# Carrier_Motor_Driver.net
KiCad netlist of a schematic drawn in EAGLE
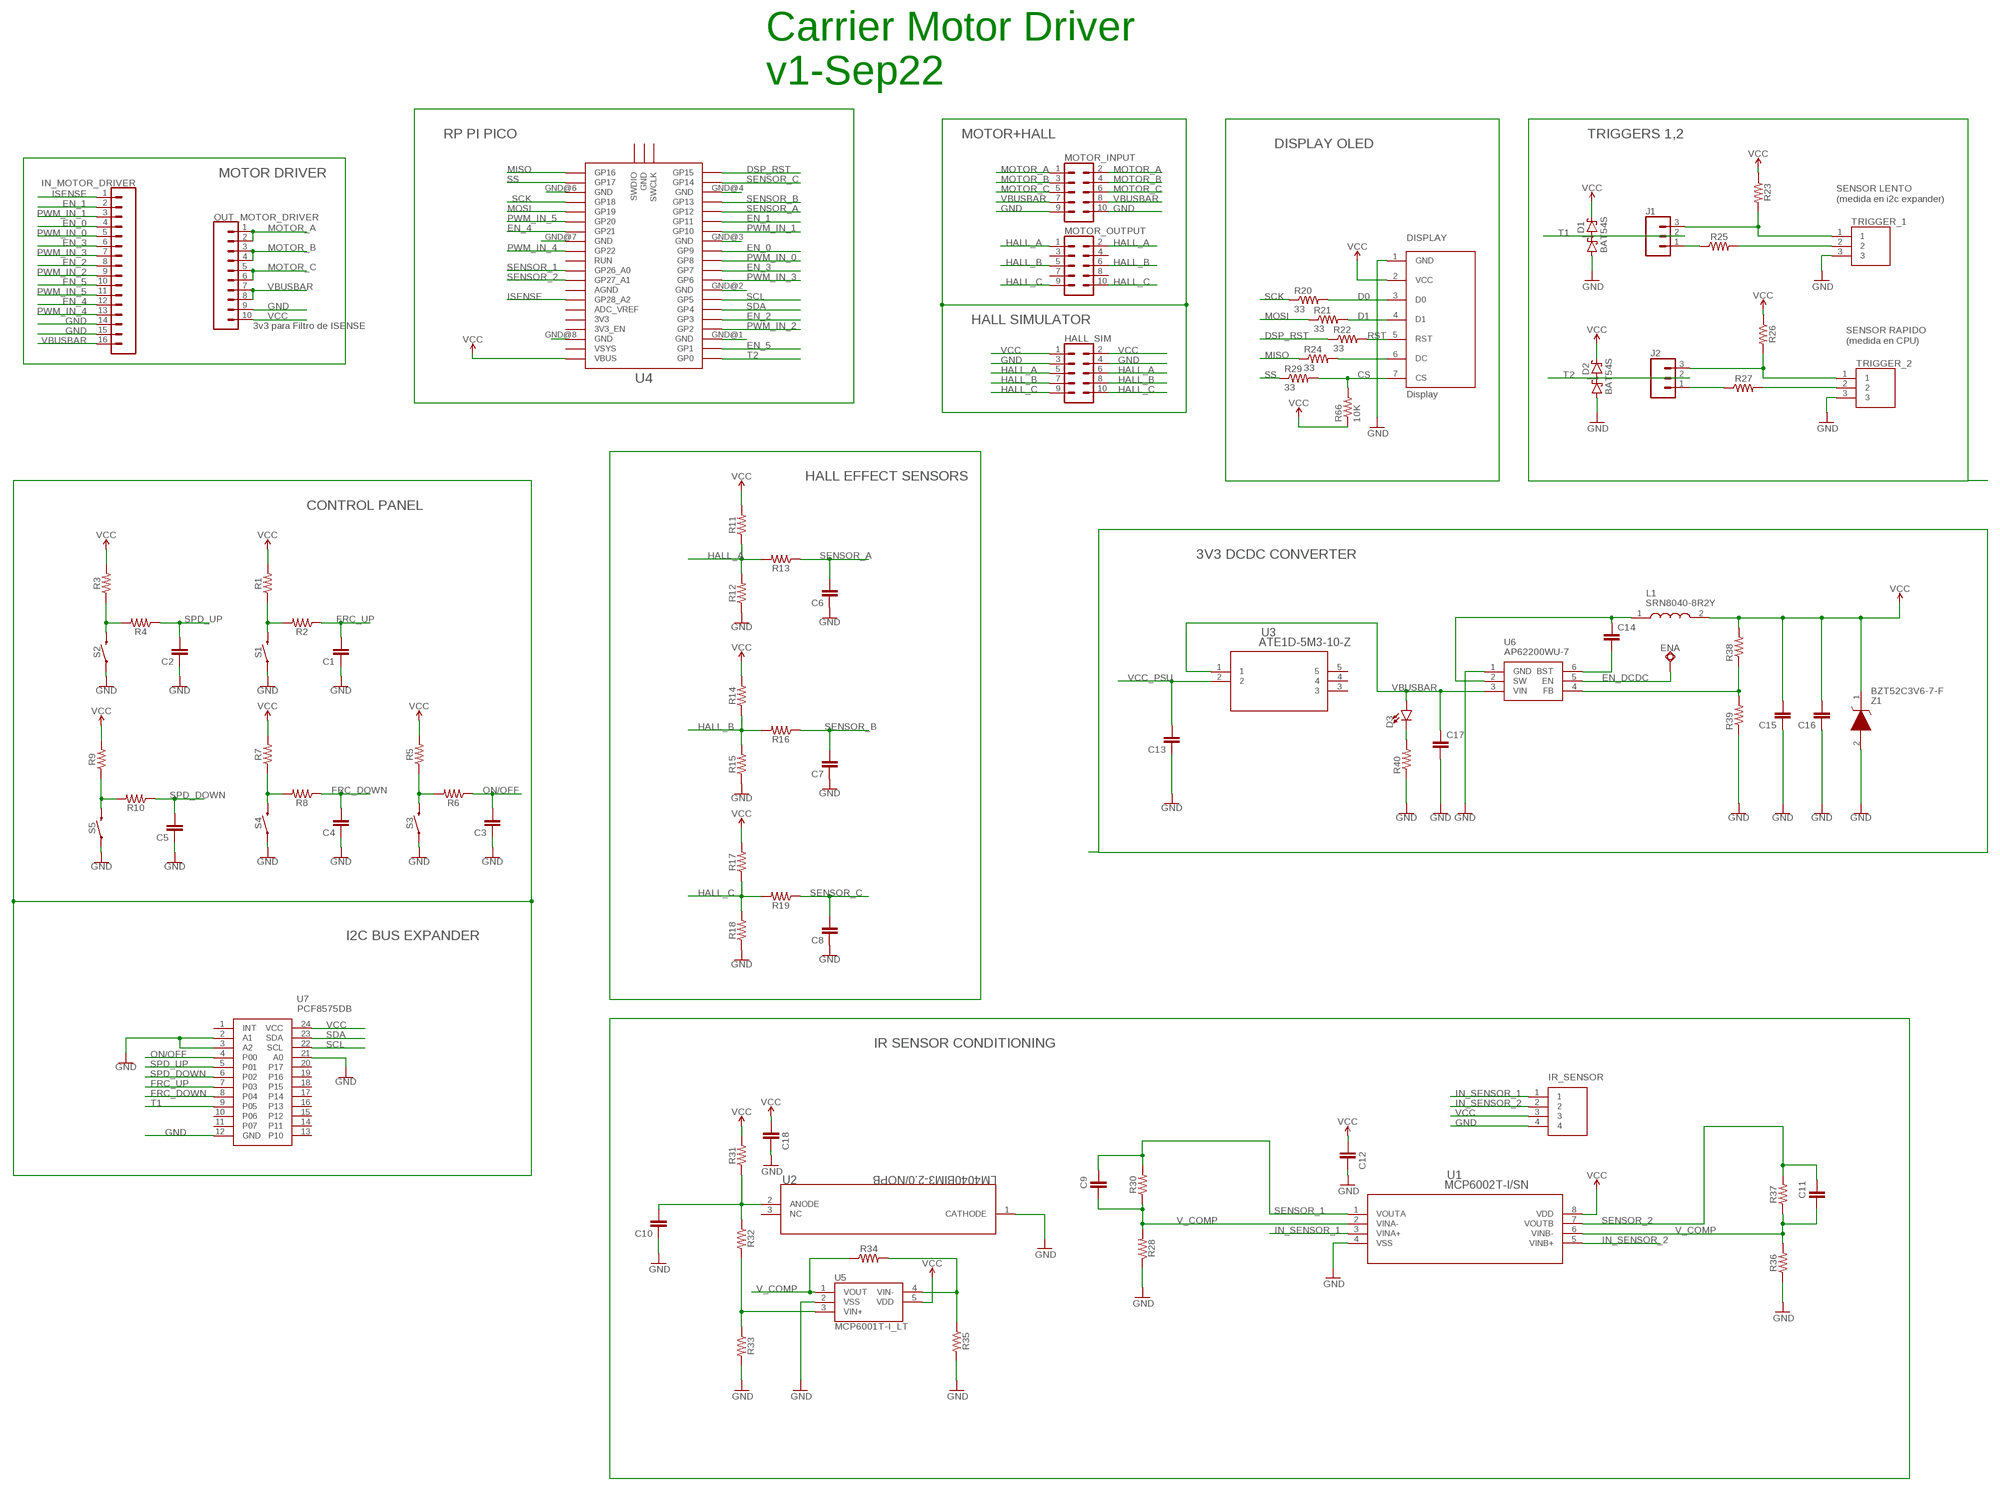
[diagram p0: schematic, sheet 1]

(export (version "E")
  (design (tool "Eeschema 10.0.6"))
  (components
    (comp (ref "C1")
      (value "C-EUC0805")
      (footprint "eagle-import:C0805")
      (libsource (lib "eagle-import") (part "C-EUC0805"))
    )
    (comp (ref "C2")
      (value "C-EUC0805")
      (footprint "eagle-import:C0805")
      (libsource (lib "eagle-import") (part "C-EUC0805"))
    )
    (comp (ref "C3")
      (value "C-EUC0805")
      (footprint "eagle-import:C0805")
      (libsource (lib "eagle-import") (part "C-EUC0805"))
    )
    (comp (ref "C4")
      (value "C-EUC0805")
      (footprint "eagle-import:C0805")
      (libsource (lib "eagle-import") (part "C-EUC0805"))
    )
    (comp (ref "C5")
      (value "C-EUC0805")
      (footprint "eagle-import:C0805")
      (libsource (lib "eagle-import") (part "C-EUC0805"))
    )
    (comp (ref "C6")
      (value "C-EUC0805")
      (footprint "eagle-import:C0805")
      (libsource (lib "eagle-import") (part "C-EUC0805"))
    )
    (comp (ref "C7")
      (value "C-EUC0805")
      (footprint "eagle-import:C0805")
      (libsource (lib "eagle-import") (part "C-EUC0805"))
    )
    (comp (ref "C8")
      (value "C-EUC0805")
      (footprint "eagle-import:C0805")
      (libsource (lib "eagle-import") (part "C-EUC0805"))
    )
    (comp (ref "C9")
      (value "C-EUC0805")
      (footprint "eagle-import:C0805")
      (libsource (lib "eagle-import") (part "C-EUC0805"))
    )
    (comp (ref "C10")
      (value "C-EUC0805")
      (footprint "eagle-import:C0805")
      (libsource (lib "eagle-import") (part "C-EUC0805"))
    )
    (comp (ref "C11")
      (value "C-EUC0805")
      (footprint "eagle-import:C0805")
      (libsource (lib "eagle-import") (part "C-EUC0805"))
    )
    (comp (ref "C12")
      (value "C-EUC0805")
      (footprint "eagle-import:C0805")
      (libsource (lib "eagle-import") (part "C-EUC0805"))
    )
    (comp (ref "C13")
      (value "C-EUC0805")
      (footprint "eagle-import:C0805")
      (libsource (lib "eagle-import") (part "C-EUC0805"))
    )
    (comp (ref "C14")
      (value "C-EUC0805")
      (footprint "eagle-import:C0805")
      (libsource (lib "eagle-import") (part "C-EUC0805"))
    )
    (comp (ref "C15")
      (value "C-EUC0805")
      (footprint "eagle-import:C0805")
      (libsource (lib "eagle-import") (part "C-EUC0805"))
    )
    (comp (ref "C16")
      (value "C-EUC0805")
      (footprint "eagle-import:C0805")
      (libsource (lib "eagle-import") (part "C-EUC0805"))
    )
    (comp (ref "C17")
      (value "C-EUC0805")
      (footprint "eagle-import:C0805")
      (libsource (lib "eagle-import") (part "C-EUC0805"))
    )
    (comp (ref "C18")
      (value "C-EUC0805")
      (footprint "eagle-import:C0805")
      (libsource (lib "eagle-import") (part "C-EUC0805"))
    )
    (comp (ref "D1")
      (value "BAT54S")
      (footprint "eagle-import:SOT23")
      (libsource (lib "eagle-import") (part "BAT54S"))
    )
    (comp (ref "D2")
      (value "BAT54S")
      (footprint "eagle-import:SOT23")
      (libsource (lib "eagle-import") (part "BAT54S"))
    )
    (comp (ref "D3")
      (value "LED3MM")
      (footprint "eagle-import:LED_3MM")
      (libsource (lib "eagle-import") (part "LED3MM"))
    )
    (comp (ref "DISPLAY")
      (value "Display")
      (footprint "eagle-import:OLED_LCD")
      (libsource (lib "eagle-import") (part "OLED_LCD"))
    )
    (comp (ref "ENA")
      (value "TESTPAD_TPSQPAD1-17")
      (footprint "eagle-import:TESTPAD_P1-17")
      (libsource (lib "eagle-import") (part "TESTPAD_TPSQPAD1-17"))
    )
    (comp (ref "HALL_SIM")
      (value "CONN_05X2NO_SILK")
      (footprint "eagle-import:2X5_NOSILK")
      (libsource (lib "eagle-import") (part "CONN_05X2NO_SILK"))
    )
    (comp (ref "IN_MOTOR_DRIVER")
      (value "CONN_16")
      (footprint "eagle-import:1X16")
      (libsource (lib "eagle-import") (part "CONN_16"))
    )
    (comp (ref "IR_SENSOR")
      (value "OSTVN04A150")
      (footprint "eagle-import:OSTVN04A150")
      (libsource (lib "eagle-import") (part "OSTVN04A150"))
    )
    (comp (ref "J1")
      (value "CONN_03")
      (footprint "eagle-import:1X03")
      (libsource (lib "eagle-import") (part "CONN_03"))
    )
    (comp (ref "J2")
      (value "CONN_03")
      (footprint "eagle-import:1X03")
      (libsource (lib "eagle-import") (part "CONN_03"))
    )
    (comp (ref "L1")
      (value "SRN8040-8R2Y")
      (footprint "eagle-import:SRN80408R2Y")
      (fields (field (name "MOUSER_PART_NUMBER") "652-SRN8040-8R2Y"))
      (libsource (lib "eagle-import") (part "SRN8040-8R2Y"))
    )
    (comp (ref "MOTOR_INPUT")
      (value "CONN_05X2PTH")
      (footprint "eagle-import:2X5")
      (libsource (lib "eagle-import") (part "CONN_05X2PTH"))
    )
    (comp (ref "MOTOR_OUTPUT")
      (value "CONN_05X2PTH")
      (footprint "eagle-import:2X5")
      (libsource (lib "eagle-import") (part "CONN_05X2PTH"))
    )
    (comp (ref "OUT_MOTOR_DRIVER")
      (value "CONN_10\"")
      (footprint "eagle-import:1X10")
      (libsource (lib "eagle-import") (part "CONN_10{dblquote}"))
    )
    (comp (ref "R1")
      (value "RESISTOR0805")
      (footprint "eagle-import:0805")
      (libsource (lib "eagle-import") (part "RESISTOR0805"))
    )
    (comp (ref "R2")
      (value "RESISTOR0805")
      (footprint "eagle-import:0805")
      (libsource (lib "eagle-import") (part "RESISTOR0805"))
    )
    (comp (ref "R3")
      (value "RESISTOR0805")
      (footprint "eagle-import:0805")
      (libsource (lib "eagle-import") (part "RESISTOR0805"))
    )
    (comp (ref "R4")
      (value "RESISTOR0805")
      (footprint "eagle-import:0805")
      (libsource (lib "eagle-import") (part "RESISTOR0805"))
    )
    (comp (ref "R5")
      (value "RESISTOR0805")
      (footprint "eagle-import:0805")
      (libsource (lib "eagle-import") (part "RESISTOR0805"))
    )
    (comp (ref "R6")
      (value "RESISTOR0805")
      (footprint "eagle-import:0805")
      (libsource (lib "eagle-import") (part "RESISTOR0805"))
    )
    (comp (ref "R7")
      (value "RESISTOR0805")
      (footprint "eagle-import:0805")
      (libsource (lib "eagle-import") (part "RESISTOR0805"))
    )
    (comp (ref "R8")
      (value "RESISTOR0805")
      (footprint "eagle-import:0805")
      (libsource (lib "eagle-import") (part "RESISTOR0805"))
    )
    (comp (ref "R9")
      (value "RESISTOR0805")
      (footprint "eagle-import:0805")
      (libsource (lib "eagle-import") (part "RESISTOR0805"))
    )
    (comp (ref "R10")
      (value "RESISTOR0805")
      (footprint "eagle-import:0805")
      (libsource (lib "eagle-import") (part "RESISTOR0805"))
    )
    (comp (ref "R11")
      (value "RESISTOR0805")
      (footprint "eagle-import:0805")
      (libsource (lib "eagle-import") (part "RESISTOR0805"))
    )
    (comp (ref "R12")
      (value "RESISTOR0805")
      (footprint "eagle-import:0805")
      (libsource (lib "eagle-import") (part "RESISTOR0805"))
    )
    (comp (ref "R13")
      (value "RESISTOR0805")
      (footprint "eagle-import:0805")
      (libsource (lib "eagle-import") (part "RESISTOR0805"))
    )
    (comp (ref "R14")
      (value "RESISTOR0805")
      (footprint "eagle-import:0805")
      (libsource (lib "eagle-import") (part "RESISTOR0805"))
    )
    (comp (ref "R15")
      (value "RESISTOR0805")
      (footprint "eagle-import:0805")
      (libsource (lib "eagle-import") (part "RESISTOR0805"))
    )
    (comp (ref "R16")
      (value "RESISTOR0805")
      (footprint "eagle-import:0805")
      (libsource (lib "eagle-import") (part "RESISTOR0805"))
    )
    (comp (ref "R17")
      (value "RESISTOR0805")
      (footprint "eagle-import:0805")
      (libsource (lib "eagle-import") (part "RESISTOR0805"))
    )
    (comp (ref "R18")
      (value "RESISTOR0805")
      (footprint "eagle-import:0805")
      (libsource (lib "eagle-import") (part "RESISTOR0805"))
    )
    (comp (ref "R19")
      (value "RESISTOR0805")
      (footprint "eagle-import:0805")
      (libsource (lib "eagle-import") (part "RESISTOR0805"))
    )
    (comp (ref "R20")
      (value "33")
      (footprint "eagle-import:0805")
      (libsource (lib "eagle-import") (part "RESISTOR0805-RES"))
    )
    (comp (ref "R21")
      (value "33")
      (footprint "eagle-import:0805")
      (libsource (lib "eagle-import") (part "RESISTOR0805-RES"))
    )
    (comp (ref "R22")
      (value "33")
      (footprint "eagle-import:0805")
      (libsource (lib "eagle-import") (part "RESISTOR0805-RES"))
    )
    (comp (ref "R23")
      (value "RESISTOR0805")
      (footprint "eagle-import:0805")
      (libsource (lib "eagle-import") (part "RESISTOR0805"))
    )
    (comp (ref "R24")
      (value "33")
      (footprint "eagle-import:0805")
      (libsource (lib "eagle-import") (part "RESISTOR0805-RES"))
    )
    (comp (ref "R25")
      (value "RESISTOR0805")
      (footprint "eagle-import:0805")
      (libsource (lib "eagle-import") (part "RESISTOR0805"))
    )
    (comp (ref "R26")
      (value "RESISTOR0805")
      (footprint "eagle-import:0805")
      (libsource (lib "eagle-import") (part "RESISTOR0805"))
    )
    (comp (ref "R27")
      (value "RESISTOR0805")
      (footprint "eagle-import:0805")
      (libsource (lib "eagle-import") (part "RESISTOR0805"))
    )
    (comp (ref "R28")
      (value "RESISTOR0805")
      (footprint "eagle-import:0805")
      (libsource (lib "eagle-import") (part "RESISTOR0805"))
    )
    (comp (ref "R29")
      (value "33")
      (footprint "eagle-import:0805")
      (libsource (lib "eagle-import") (part "RESISTOR0805-RES"))
    )
    (comp (ref "R30")
      (value "RESISTOR0805")
      (footprint "eagle-import:0805")
      (libsource (lib "eagle-import") (part "RESISTOR0805"))
    )
    (comp (ref "R31")
      (value "RESISTOR0805")
      (footprint "eagle-import:0805")
      (libsource (lib "eagle-import") (part "RESISTOR0805"))
    )
    (comp (ref "R32")
      (value "RESISTOR0805")
      (footprint "eagle-import:0805")
      (libsource (lib "eagle-import") (part "RESISTOR0805"))
    )
    (comp (ref "R33")
      (value "RESISTOR0805")
      (footprint "eagle-import:0805")
      (libsource (lib "eagle-import") (part "RESISTOR0805"))
    )
    (comp (ref "R34")
      (value "RESISTOR0805")
      (footprint "eagle-import:0805")
      (libsource (lib "eagle-import") (part "RESISTOR0805"))
    )
    (comp (ref "R35")
      (value "RESISTOR0805")
      (footprint "eagle-import:0805")
      (libsource (lib "eagle-import") (part "RESISTOR0805"))
    )
    (comp (ref "R36")
      (value "RESISTOR0805")
      (footprint "eagle-import:0805")
      (libsource (lib "eagle-import") (part "RESISTOR0805"))
    )
    (comp (ref "R37")
      (value "RESISTOR0805")
      (footprint "eagle-import:0805")
      (libsource (lib "eagle-import") (part "RESISTOR0805"))
    )
    (comp (ref "R38")
      (value "10K")
      (footprint "eagle-import:0805")
      (libsource (lib "eagle-import") (part "RESISTOR0805-RES"))
    )
    (comp (ref "R39")
      (value "10K")
      (footprint "eagle-import:0805")
      (libsource (lib "eagle-import") (part "RESISTOR0805-RES"))
    )
    (comp (ref "R40")
      (value "10K")
      (footprint "eagle-import:0805")
      (libsource (lib "eagle-import") (part "RESISTOR0805-RES"))
    )
    (comp (ref "R66")
      (value "10K")
      (footprint "eagle-import:0805")
      (libsource (lib "eagle-import") (part "RESISTOR0805-RES"))
    )
    (comp (ref "S1")
      (value "MOMENTARY-SWITCH-SPST-SMD-5.2MM")
      (footprint "eagle-import:TACTILE_SWITCH_SMD_5.2MM")
      (libsource (lib "eagle-import") (part "MOMENTARY-SWITCH-SPST-SMD-5.2MM"))
    )
    (comp (ref "S2")
      (value "MOMENTARY-SWITCH-SPST-SMD-5.2MM")
      (footprint "eagle-import:TACTILE_SWITCH_SMD_5.2MM")
      (libsource (lib "eagle-import") (part "MOMENTARY-SWITCH-SPST-SMD-5.2MM"))
    )
    (comp (ref "S3")
      (value "MOMENTARY-SWITCH-SPST-SMD-5.2MM")
      (footprint "eagle-import:TACTILE_SWITCH_SMD_5.2MM")
      (libsource (lib "eagle-import") (part "MOMENTARY-SWITCH-SPST-SMD-5.2MM"))
    )
    (comp (ref "S4")
      (value "MOMENTARY-SWITCH-SPST-SMD-5.2MM")
      (footprint "eagle-import:TACTILE_SWITCH_SMD_5.2MM")
      (libsource (lib "eagle-import") (part "MOMENTARY-SWITCH-SPST-SMD-5.2MM"))
    )
    (comp (ref "S5")
      (value "MOMENTARY-SWITCH-SPST-SMD-5.2MM")
      (footprint "eagle-import:TACTILE_SWITCH_SMD_5.2MM")
      (libsource (lib "eagle-import") (part "MOMENTARY-SWITCH-SPST-SMD-5.2MM"))
    )
    (comp (ref "TRIGGER_1")
      (value "OSTVN03A150")
      (footprint "eagle-import:OSTVN03A150")
      (libsource (lib "eagle-import") (part "OSTVN03A150"))
    )
    (comp (ref "TRIGGER_2")
      (value "OSTVN03A150")
      (footprint "eagle-import:OSTVN03A150")
      (libsource (lib "eagle-import") (part "OSTVN03A150"))
    )
    (comp (ref "U1")
      (value "MCP6002T-I/SN")
      (footprint "eagle-import:SOIC8-N_MC_MCH")
      (fields (field (name "COPYRIGHT") "Copyright (C) 2022 Ultra Librarian. All rights reserved."))
      (libsource (lib "eagle-import") (part "MCP6002T-I/SN"))
    )
    (comp (ref "U2")
      (value "LM4040BIM3-2.0/NOPB")
      (footprint "eagle-import:DBZ3")
      (fields
        (field (name "GENERIC_PART_NUMBER") "LM4040D50")
        (field (name "MANUFACTURER") "Texas Instruments")
      )
      (libsource (lib "eagle-import") (part "LM4040BIM3-2.0/NOPB"))
    )
    (comp (ref "U3")
      (value "ATE1D-5M3-10-Z")
      (footprint "eagle-import:SPDT05_ATE1D_9P5X8_NDC")
      (fields (field (name "COPYRIGHT") "Copyright (C) 2022 Ultra Librarian. All rights reserved."))
      (libsource (lib "eagle-import") (part "ATE1D-5M3-10-Z"))
    )
    (comp (ref "U4")
      (value "RPI_PICO_IG-SMD")
      (footprint "eagle-import:RPI_PICO")
      (libsource (lib "eagle-import") (part "RPI_PICO_IG-SMD"))
    )
    (comp (ref "U5")
      (value "MCP6001T-I_LT")
      (footprint "eagle-import:SOT65P210X110-5N")
      (fields
        (field (name "ARROW_PART_NUMBER") "MCP6001T-I/LT")
        (field (name "MOUSER_PART_NUMBER") "579-MCP6001T-I/LT")
      )
      (libsource (lib "eagle-import") (part "MCP6001T-I_LT"))
    )
    (comp (ref "U6")
      (value "AP62200WU-7")
      (footprint "eagle-import:SOT95P280X100-6N")
      (fields (field (name "MOUSER_PART_NUMBER") "621-AP62200WU-7"))
      (libsource (lib "eagle-import") (part "AP62200WU-7"))
    )
    (comp (ref "U7")
      (value "PCF8575DB")
      (footprint "eagle-import:SOP65P780X200-24N")
      (fields (field (name "MOUSER_PART_NUMBER") "595-PCF8575DB"))
      (libsource (lib "eagle-import") (part "PCF8575DB"))
    )
    (comp (ref "Z1")
      (value "BZT52C3V6-7-F")
      (footprint "eagle-import:SOD3716X135N")
      (fields (field (name "MOUSER_PART_NUMBER") "621-BZT52C3V6-F"))
      (libsource (lib "eagle-import") (part "BZT52C3V6-7-F"))
    )
  )
  (nets
    (net (code "1") (name "/CS") (class "Default")
      (node (ref "DISPLAY") (pin "7") (pinfunction "CS_7") (pintype "bidirectional"))
      (node (ref "R29") (pin "2") (pinfunction "2_2") (pintype "passive"))
      (node (ref "R66") (pin "2") (pinfunction "2_2") (pintype "passive"))
    )
    (net (code "2") (name "/D0") (class "Default")
      (node (ref "DISPLAY") (pin "3") (pinfunction "D0_3") (pintype "bidirectional"))
      (node (ref "R20") (pin "2") (pinfunction "2_2") (pintype "passive"))
    )
    (net (code "3") (name "/D1") (class "Default")
      (node (ref "DISPLAY") (pin "4") (pinfunction "D1_4") (pintype "bidirectional"))
      (node (ref "R21") (pin "2") (pinfunction "2_2") (pintype "passive"))
    )
    (net (code "4") (name "/DSP_RST") (class "Default")
      (node (ref "R22") (pin "1") (pinfunction "1_1") (pintype "passive"))
      (node (ref "U4") (pin "GP15") (pinfunction "GP15_GP15") (pintype "bidirectional"))
    )
    (net (code "5") (name "/EN_0") (class "Default")
      (node (ref "IN_MOTOR_DRIVER") (pin "4") (pinfunction "4_4") (pintype "passive"))
      (node (ref "U4") (pin "GP9") (pinfunction "GP9_GP9") (pintype "bidirectional"))
    )
    (net (code "6") (name "/EN_1") (class "Default")
      (node (ref "IN_MOTOR_DRIVER") (pin "2") (pinfunction "2_2") (pintype "passive"))
      (node (ref "U4") (pin "GP11") (pinfunction "GP11_GP11") (pintype "bidirectional"))
    )
    (net (code "7") (name "/EN_2") (class "Default")
      (node (ref "IN_MOTOR_DRIVER") (pin "8") (pinfunction "8_8") (pintype "passive"))
      (node (ref "U4") (pin "GP3") (pinfunction "GP3_GP3") (pintype "bidirectional"))
    )
    (net (code "8") (name "/EN_3") (class "Default")
      (node (ref "IN_MOTOR_DRIVER") (pin "6") (pinfunction "6_6") (pintype "passive"))
      (node (ref "U4") (pin "GP7") (pinfunction "GP7_GP7") (pintype "bidirectional"))
    )
    (net (code "9") (name "/EN_4") (class "Default")
      (node (ref "IN_MOTOR_DRIVER") (pin "12") (pinfunction "12_12") (pintype "passive"))
      (node (ref "U4") (pin "GP21") (pinfunction "GP21_GP21") (pintype "bidirectional"))
    )
    (net (code "10") (name "/EN_5") (class "Default")
      (node (ref "IN_MOTOR_DRIVER") (pin "10") (pinfunction "10_10") (pintype "passive"))
      (node (ref "U4") (pin "GP1") (pinfunction "GP1_GP1") (pintype "bidirectional"))
    )
    (net (code "11") (name "/EN_DCDC") (class "Default")
      (node (ref "ENA") (pin "TP") (pinfunction "TP_TP") (pintype "input"))
      (node (ref "U6") (pin "5") (pinfunction "EN_5") (pintype "bidirectional"))
    )
    (net (code "12") (name "/FRC_DOWN") (class "Default")
      (node (ref "C4") (pin "2") (pinfunction "2_2") (pintype "passive"))
      (node (ref "R8") (pin "1") (pinfunction "1_1") (pintype "passive"))
      (node (ref "U7") (pin "8") (pinfunction "P04_8") (pintype "bidirectional"))
    )
    (net (code "13") (name "/FRC_UP") (class "Default")
      (node (ref "C1") (pin "2") (pinfunction "2_2") (pintype "passive"))
      (node (ref "R2") (pin "1") (pinfunction "1_1") (pintype "passive"))
      (node (ref "U7") (pin "7") (pinfunction "P03_7") (pintype "bidirectional"))
    )
    (net (code "14") (name "/HALL_A") (class "Default")
      (node (ref "HALL_SIM") (pin "5") (pinfunction "5_5") (pintype "passive"))
      (node (ref "HALL_SIM") (pin "6") (pinfunction "6_6") (pintype "passive"))
      (node (ref "MOTOR_OUTPUT") (pin "1") (pinfunction "1_1") (pintype "passive"))
      (node (ref "MOTOR_OUTPUT") (pin "2") (pinfunction "2_2") (pintype "passive"))
      (node (ref "R11") (pin "1") (pinfunction "1_1") (pintype "passive"))
      (node (ref "R12") (pin "2") (pinfunction "2_2") (pintype "passive"))
      (node (ref "R13") (pin "2") (pinfunction "2_2") (pintype "passive"))
    )
    (net (code "15") (name "/HALL_B") (class "Default")
      (node (ref "HALL_SIM") (pin "7") (pinfunction "7_7") (pintype "passive"))
      (node (ref "HALL_SIM") (pin "8") (pinfunction "8_8") (pintype "passive"))
      (node (ref "MOTOR_OUTPUT") (pin "5") (pinfunction "5_5") (pintype "passive"))
      (node (ref "MOTOR_OUTPUT") (pin "6") (pinfunction "6_6") (pintype "passive"))
      (node (ref "R14") (pin "1") (pinfunction "1_1") (pintype "passive"))
      (node (ref "R15") (pin "2") (pinfunction "2_2") (pintype "passive"))
      (node (ref "R16") (pin "2") (pinfunction "2_2") (pintype "passive"))
    )
    (net (code "16") (name "/HALL_C") (class "Default")
      (node (ref "HALL_SIM") (pin "10") (pinfunction "10_10") (pintype "passive"))
      (node (ref "HALL_SIM") (pin "9") (pinfunction "9_9") (pintype "passive"))
      (node (ref "MOTOR_OUTPUT") (pin "10") (pinfunction "10_10") (pintype "passive"))
      (node (ref "MOTOR_OUTPUT") (pin "9") (pinfunction "9_9") (pintype "passive"))
      (node (ref "R17") (pin "1") (pinfunction "1_1") (pintype "passive"))
      (node (ref "R18") (pin "2") (pinfunction "2_2") (pintype "passive"))
      (node (ref "R19") (pin "2") (pinfunction "2_2") (pintype "passive"))
    )
    (net (code "17") (name "/IN_SENSOR_1") (class "Default")
      (node (ref "IR_SENSOR") (pin "1") (pinfunction "1_1") (pintype "bidirectional"))
      (node (ref "U1") (pin "3") (pinfunction "VINA+_3") (pintype "input"))
    )
    (net (code "18") (name "/IN_SENSOR_2") (class "Default")
      (node (ref "IR_SENSOR") (pin "2") (pinfunction "2_2") (pintype "bidirectional"))
      (node (ref "U1") (pin "5") (pinfunction "VINB+_5") (pintype "input"))
    )
    (net (code "19") (name "/ISENSE") (class "Default")
      (node (ref "IN_MOTOR_DRIVER") (pin "1") (pinfunction "1_1") (pintype "passive"))
      (node (ref "U4") (pin "GP28_A2") (pinfunction "GP28_A2_GP28_A2") (pintype "bidirectional"))
    )
    (net (code "20") (name "/MISO") (class "Default")
      (node (ref "R24") (pin "1") (pinfunction "1_1") (pintype "passive"))
      (node (ref "U4") (pin "GP16") (pinfunction "GP16_GP16") (pintype "bidirectional"))
    )
    (net (code "21") (name "/MOSI") (class "Default")
      (node (ref "R21") (pin "1") (pinfunction "1_1") (pintype "passive"))
      (node (ref "U4") (pin "GP19") (pinfunction "GP19_GP19") (pintype "bidirectional"))
    )
    (net (code "22") (name "/MOTOR_A") (class "Default")
      (node (ref "MOTOR_INPUT") (pin "1") (pinfunction "1_1") (pintype "passive"))
      (node (ref "MOTOR_INPUT") (pin "2") (pinfunction "2_2") (pintype "passive"))
      (node (ref "OUT_MOTOR_DRIVER") (pin "1") (pinfunction "1_1") (pintype "passive"))
      (node (ref "OUT_MOTOR_DRIVER") (pin "2") (pinfunction "2_2") (pintype "passive"))
    )
    (net (code "23") (name "/MOTOR_B") (class "Default")
      (node (ref "MOTOR_INPUT") (pin "3") (pinfunction "3_3") (pintype "passive"))
      (node (ref "MOTOR_INPUT") (pin "4") (pinfunction "4_4") (pintype "passive"))
      (node (ref "OUT_MOTOR_DRIVER") (pin "3") (pinfunction "3_3") (pintype "passive"))
      (node (ref "OUT_MOTOR_DRIVER") (pin "4") (pinfunction "4_4") (pintype "passive"))
    )
    (net (code "24") (name "/MOTOR_C") (class "Default")
      (node (ref "MOTOR_INPUT") (pin "5") (pinfunction "5_5") (pintype "passive"))
      (node (ref "MOTOR_INPUT") (pin "6") (pinfunction "6_6") (pintype "passive"))
      (node (ref "OUT_MOTOR_DRIVER") (pin "5") (pinfunction "5_5") (pintype "passive"))
      (node (ref "OUT_MOTOR_DRIVER") (pin "6") (pinfunction "6_6") (pintype "passive"))
    )
    (net (code "25") (name "/ON{slash}OFF") (class "Default")
      (node (ref "C3") (pin "2") (pinfunction "2_2") (pintype "passive"))
      (node (ref "R6") (pin "1") (pinfunction "1_1") (pintype "passive"))
      (node (ref "U7") (pin "4") (pinfunction "P00_4") (pintype "bidirectional"))
    )
    (net (code "26") (name "/PWM_IN_0") (class "Default")
      (node (ref "IN_MOTOR_DRIVER") (pin "5") (pinfunction "5_5") (pintype "passive"))
      (node (ref "U4") (pin "GP8") (pinfunction "GP8_GP8") (pintype "bidirectional"))
    )
    (net (code "27") (name "/PWM_IN_1") (class "Default")
      (node (ref "IN_MOTOR_DRIVER") (pin "3") (pinfunction "3_3") (pintype "passive"))
      (node (ref "U4") (pin "GP10") (pinfunction "GP10_GP10") (pintype "bidirectional"))
    )
    (net (code "28") (name "/PWM_IN_2") (class "Default")
      (node (ref "IN_MOTOR_DRIVER") (pin "9") (pinfunction "9_9") (pintype "passive"))
      (node (ref "U4") (pin "GP2") (pinfunction "GP2_GP2") (pintype "bidirectional"))
    )
    (net (code "29") (name "/PWM_IN_3") (class "Default")
      (node (ref "IN_MOTOR_DRIVER") (pin "7") (pinfunction "7_7") (pintype "passive"))
      (node (ref "U4") (pin "GP6") (pinfunction "GP6_GP6") (pintype "bidirectional"))
    )
    (net (code "30") (name "/PWM_IN_4") (class "Default")
      (node (ref "IN_MOTOR_DRIVER") (pin "13") (pinfunction "13_13") (pintype "passive"))
      (node (ref "U4") (pin "GP22") (pinfunction "GP22_GP22") (pintype "bidirectional"))
    )
    (net (code "31") (name "/PWM_IN_5") (class "Default")
      (node (ref "IN_MOTOR_DRIVER") (pin "11") (pinfunction "11_11") (pintype "passive"))
      (node (ref "U4") (pin "GP20") (pinfunction "GP20_GP20") (pintype "bidirectional"))
    )
    (net (code "32") (name "/RST") (class "Default")
      (node (ref "DISPLAY") (pin "5") (pinfunction "RST_5") (pintype "bidirectional"))
      (node (ref "R22") (pin "2") (pinfunction "2_2") (pintype "passive"))
    )
    (net (code "33") (name "/SCK") (class "Default")
      (node (ref "R20") (pin "1") (pinfunction "1_1") (pintype "passive"))
      (node (ref "U4") (pin "GP18") (pinfunction "GP18_GP18") (pintype "bidirectional"))
    )
    (net (code "34") (name "/SCL") (class "Default")
      (node (ref "U4") (pin "GP5") (pinfunction "GP5_GP5") (pintype "bidirectional"))
      (node (ref "U7") (pin "22") (pinfunction "SCL_22") (pintype "bidirectional"))
    )
    (net (code "35") (name "/SDA") (class "Default")
      (node (ref "U4") (pin "GP4") (pinfunction "GP4_GP4") (pintype "bidirectional"))
      (node (ref "U7") (pin "23") (pinfunction "SDA_23") (pintype "bidirectional"))
    )
    (net (code "36") (name "/SENSOR_1") (class "Default")
      (node (ref "C9") (pin "1") (pinfunction "1_1") (pintype "passive"))
      (node (ref "R30") (pin "2") (pinfunction "2_2") (pintype "passive"))
      (node (ref "U1") (pin "1") (pinfunction "VOUTA_1") (pintype "output"))
      (node (ref "U4") (pin "GP26_A0") (pinfunction "GP26_A0_GP26_A0") (pintype "bidirectional"))
    )
    (net (code "37") (name "/SENSOR_2") (class "Default")
      (node (ref "C11") (pin "1") (pinfunction "1_1") (pintype "passive"))
      (node (ref "R37") (pin "2") (pinfunction "2_2") (pintype "passive"))
      (node (ref "U1") (pin "7") (pinfunction "VOUTB_7") (pintype "output"))
      (node (ref "U4") (pin "GP27_A1") (pinfunction "GP27_A1_GP27_A1") (pintype "bidirectional"))
    )
    (net (code "38") (name "/SENSOR_A") (class "Default")
      (node (ref "C6") (pin "2") (pinfunction "2_2") (pintype "passive"))
      (node (ref "R13") (pin "1") (pinfunction "1_1") (pintype "passive"))
      (node (ref "U4") (pin "GP12") (pinfunction "GP12_GP12") (pintype "bidirectional"))
    )
    (net (code "39") (name "/SENSOR_B") (class "Default")
      (node (ref "C7") (pin "2") (pinfunction "2_2") (pintype "passive"))
      (node (ref "R16") (pin "1") (pinfunction "1_1") (pintype "passive"))
      (node (ref "U4") (pin "GP13") (pinfunction "GP13_GP13") (pintype "bidirectional"))
    )
    (net (code "40") (name "/SENSOR_C") (class "Default")
      (node (ref "C8") (pin "2") (pinfunction "2_2") (pintype "passive"))
      (node (ref "R19") (pin "1") (pinfunction "1_1") (pintype "passive"))
      (node (ref "U4") (pin "GP14") (pinfunction "GP14_GP14") (pintype "bidirectional"))
    )
    (net (code "41") (name "/SPD_DOWN") (class "Default")
      (node (ref "C5") (pin "2") (pinfunction "2_2") (pintype "passive"))
      (node (ref "R10") (pin "1") (pinfunction "1_1") (pintype "passive"))
      (node (ref "U7") (pin "6") (pinfunction "P02_6") (pintype "bidirectional"))
    )
    (net (code "42") (name "/SPD_UP") (class "Default")
      (node (ref "C2") (pin "2") (pinfunction "2_2") (pintype "passive"))
      (node (ref "R4") (pin "1") (pinfunction "1_1") (pintype "passive"))
      (node (ref "U7") (pin "5") (pinfunction "P01_5") (pintype "bidirectional"))
    )
    (net (code "43") (name "/SS") (class "Default")
      (node (ref "R29") (pin "1") (pinfunction "1_1") (pintype "passive"))
      (node (ref "U4") (pin "GP17") (pinfunction "GP17_GP17") (pintype "bidirectional"))
    )
    (net (code "44") (name "/T1") (class "Default")
      (node (ref "D1") (pin "3") (pinfunction "C1A2_3") (pintype "passive"))
      (node (ref "J1") (pin "2") (pinfunction "2_2") (pintype "passive"))
      (node (ref "U7") (pin "9") (pinfunction "P05_9") (pintype "bidirectional"))
    )
    (net (code "45") (name "/T2") (class "Default")
      (node (ref "D2") (pin "3") (pinfunction "C1A2_3") (pintype "passive"))
      (node (ref "J2") (pin "2") (pinfunction "2_2") (pintype "passive"))
      (node (ref "U4") (pin "GP0") (pinfunction "GP0_GP0") (pintype "bidirectional"))
    )
    (net (code "46") (name "/VBUSBAR") (class "Default")
      (node (ref "C17") (pin "1") (pinfunction "1_1") (pintype "passive"))
      (node (ref "D3") (pin "A") (pinfunction "A_A") (pintype "passive"))
      (node (ref "IN_MOTOR_DRIVER") (pin "16") (pinfunction "16_16") (pintype "passive"))
      (node (ref "MOTOR_INPUT") (pin "7") (pinfunction "7_7") (pintype "passive"))
      (node (ref "MOTOR_INPUT") (pin "8") (pinfunction "8_8") (pintype "passive"))
      (node (ref "OUT_MOTOR_DRIVER") (pin "7") (pinfunction "7_7") (pintype "passive"))
      (node (ref "OUT_MOTOR_DRIVER") (pin "8") (pinfunction "8_8") (pintype "passive"))
      (node (ref "U3") (pin "1") (pinfunction "1_1") (pintype "passive"))
      (node (ref "U6") (pin "3") (pinfunction "VIN_3") (pintype "bidirectional"))
    )
    (net (code "47") (name "/VCC_PSU") (class "Default")
      (node (ref "C13") (pin "2") (pinfunction "2_2") (pintype "passive"))
      (node (ref "U3") (pin "2") (pinfunction "2_2") (pintype "passive"))
    )
    (net (code "48") (name "/V_COMP") (class "Default")
      (node (ref "C11") (pin "2") (pinfunction "2_2") (pintype "passive"))
      (node (ref "C9") (pin "2") (pinfunction "2_2") (pintype "passive"))
      (node (ref "R28") (pin "2") (pinfunction "2_2") (pintype "passive"))
      (node (ref "R30") (pin "1") (pinfunction "1_1") (pintype "passive"))
      (node (ref "R34") (pin "1") (pinfunction "1_1") (pintype "passive"))
      (node (ref "R36") (pin "2") (pinfunction "2_2") (pintype "passive"))
      (node (ref "R37") (pin "1") (pinfunction "1_1") (pintype "passive"))
      (node (ref "U1") (pin "2") (pinfunction "VINA-_2") (pintype "input"))
      (node (ref "U1") (pin "6") (pinfunction "VINB-_6") (pintype "input"))
      (node (ref "U5") (pin "1") (pinfunction "VOUT_1") (pintype "bidirectional"))
    )
    (net (code "49") (name "GND") (class "Default")
      (node (ref "C1") (pin "1") (pinfunction "1_1") (pintype "passive"))
      (node (ref "C10") (pin "1") (pinfunction "1_1") (pintype "passive"))
      (node (ref "C12") (pin "1") (pinfunction "1_1") (pintype "passive"))
      (node (ref "C13") (pin "1") (pinfunction "1_1") (pintype "passive"))
      (node (ref "C15") (pin "1") (pinfunction "1_1") (pintype "passive"))
      (node (ref "C16") (pin "1") (pinfunction "1_1") (pintype "passive"))
      (node (ref "C17") (pin "2") (pinfunction "2_2") (pintype "passive"))
      (node (ref "C18") (pin "1") (pinfunction "1_1") (pintype "passive"))
      (node (ref "C2") (pin "1") (pinfunction "1_1") (pintype "passive"))
      (node (ref "C3") (pin "1") (pinfunction "1_1") (pintype "passive"))
      (node (ref "C4") (pin "1") (pinfunction "1_1") (pintype "passive"))
      (node (ref "C5") (pin "1") (pinfunction "1_1") (pintype "passive"))
      (node (ref "C6") (pin "1") (pinfunction "1_1") (pintype "passive"))
      (node (ref "C7") (pin "1") (pinfunction "1_1") (pintype "passive"))
      (node (ref "C8") (pin "1") (pinfunction "1_1") (pintype "passive"))
      (node (ref "D1") (pin "1") (pinfunction "A1_1") (pintype "passive"))
      (node (ref "D2") (pin "1") (pinfunction "A1_1") (pintype "passive"))
      (node (ref "DISPLAY") (pin "1") (pinfunction "GND_1") (pintype "bidirectional"))
      (node (ref "HALL_SIM") (pin "3") (pinfunction "3_3") (pintype "passive"))
      (node (ref "HALL_SIM") (pin "4") (pinfunction "4_4") (pintype "passive"))
      (node (ref "IN_MOTOR_DRIVER") (pin "14") (pinfunction "14_14") (pintype "passive"))
      (node (ref "IN_MOTOR_DRIVER") (pin "15") (pinfunction "15_15") (pintype "passive"))
      (node (ref "IR_SENSOR") (pin "4") (pinfunction "4_4") (pintype "bidirectional"))
      (node (ref "MOTOR_INPUT") (pin "10") (pinfunction "10_10") (pintype "passive"))
      (node (ref "MOTOR_INPUT") (pin "9") (pinfunction "9_9") (pintype "passive"))
      (node (ref "OUT_MOTOR_DRIVER") (pin "9") (pinfunction "9_9") (pintype "passive"))
      (node (ref "R12") (pin "1") (pinfunction "1_1") (pintype "passive"))
      (node (ref "R15") (pin "1") (pinfunction "1_1") (pintype "passive"))
      (node (ref "R18") (pin "1") (pinfunction "1_1") (pintype "passive"))
      (node (ref "R28") (pin "1") (pinfunction "1_1") (pintype "passive"))
      (node (ref "R33") (pin "2") (pinfunction "2_2") (pintype "passive"))
      (node (ref "R35") (pin "2") (pinfunction "2_2") (pintype "passive"))
      (node (ref "R36") (pin "1") (pinfunction "1_1") (pintype "passive"))
      (node (ref "R39") (pin "1") (pinfunction "1_1") (pintype "passive"))
      (node (ref "R40") (pin "1") (pinfunction "1_1") (pintype "passive"))
      (node (ref "S1") (pin "1") (pinfunction "1_1") (pintype "passive"))
      (node (ref "S2") (pin "1") (pinfunction "1_1") (pintype "passive"))
      (node (ref "S3") (pin "1") (pinfunction "1_1") (pintype "passive"))
      (node (ref "S4") (pin "1") (pinfunction "1_1") (pintype "passive"))
      (node (ref "S5") (pin "1") (pinfunction "1_1") (pintype "passive"))
      (node (ref "TRIGGER_1") (pin "3") (pinfunction "3_3") (pintype "bidirectional"))
      (node (ref "TRIGGER_2") (pin "3") (pinfunction "3_3") (pintype "bidirectional"))
      (node (ref "U1") (pin "4") (pinfunction "VSS_4") (pintype "passive"))
      (node (ref "U2") (pin "1") (pinfunction "CATHODE_1") (pintype "passive"))
      (node (ref "U4") (pin "GND@1") (pinfunction "GND_GND@1") (pintype "bidirectional"))
      (node (ref "U4") (pin "GND@2") (pinfunction "GND_GND@2") (pintype "bidirectional"))
      (node (ref "U4") (pin "GND@3") (pinfunction "GND_GND@3") (pintype "bidirectional"))
      (node (ref "U4") (pin "GND@4") (pinfunction "GND_GND@4") (pintype "bidirectional"))
      (node (ref "U4") (pin "GND@6") (pinfunction "GND_GND@6") (pintype "bidirectional"))
      (node (ref "U4") (pin "GND@7") (pinfunction "GND_GND@7") (pintype "bidirectional"))
      (node (ref "U4") (pin "GND@8") (pinfunction "GND_GND@8") (pintype "bidirectional"))
      (node (ref "U5") (pin "2") (pinfunction "VSS_2") (pintype "bidirectional"))
      (node (ref "U6") (pin "1") (pinfunction "GND_1") (pintype "bidirectional"))
      (node (ref "U7") (pin "12") (pinfunction "GND_12") (pintype "bidirectional"))
      (node (ref "U7") (pin "2") (pinfunction "A1_2") (pintype "bidirectional"))
      (node (ref "U7") (pin "21") (pinfunction "A0_21") (pintype "bidirectional"))
      (node (ref "U7") (pin "3") (pinfunction "A2_3") (pintype "bidirectional"))
      (node (ref "Z1") (pin "2") (pinfunction "A_2") (pintype "bidirectional"))
    )
    (net (code "50") (name "Net-(D3-C)") (class "Default")
      (node (ref "D3") (pin "K") (pinfunction "C_K") (pintype "passive"))
      (node (ref "R40") (pin "2") (pinfunction "2_2") (pintype "passive"))
    )
    (net (code "51") (name "Net-(DISPLAY-DC)") (class "Default")
      (node (ref "DISPLAY") (pin "6") (pinfunction "DC_6") (pintype "bidirectional"))
      (node (ref "R24") (pin "2") (pinfunction "2_2") (pintype "passive"))
    )
    (net (code "52") (name "Net-(J1-Pad1)") (class "Default")
      (node (ref "J1") (pin "1") (pinfunction "1_1") (pintype "passive"))
      (node (ref "R25") (pin "1") (pinfunction "1_1") (pintype "passive"))
    )
    (net (code "53") (name "Net-(J1-Pad3)") (class "Default")
      (node (ref "J1") (pin "3") (pinfunction "3_3") (pintype "passive"))
      (node (ref "R23") (pin "2") (pinfunction "2_2") (pintype "passive"))
      (node (ref "TRIGGER_1") (pin "1") (pinfunction "1_1") (pintype "bidirectional"))
    )
    (net (code "54") (name "Net-(J2-Pad1)") (class "Default")
      (node (ref "J2") (pin "1") (pinfunction "1_1") (pintype "passive"))
      (node (ref "R27") (pin "1") (pinfunction "1_1") (pintype "passive"))
    )
    (net (code "55") (name "Net-(J2-Pad3)") (class "Default")
      (node (ref "J2") (pin "3") (pinfunction "3_3") (pintype "passive"))
      (node (ref "R26") (pin "2") (pinfunction "2_2") (pintype "passive"))
      (node (ref "TRIGGER_2") (pin "1") (pinfunction "1_1") (pintype "bidirectional"))
    )
    (net (code "56") (name "Net-(R25-Pad2)") (class "Default")
      (node (ref "R25") (pin "2") (pinfunction "2_2") (pintype "passive"))
      (node (ref "TRIGGER_1") (pin "2") (pinfunction "2_2") (pintype "bidirectional"))
    )
    (net (code "57") (name "Net-(R27-Pad2)") (class "Default")
      (node (ref "R27") (pin "2") (pinfunction "2_2") (pintype "passive"))
      (node (ref "TRIGGER_2") (pin "2") (pinfunction "2_2") (pintype "bidirectional"))
    )
    (net (code "58") (name "Net-(S1-2)") (class "Default")
      (node (ref "R1") (pin "1") (pinfunction "1_1") (pintype "passive"))
      (node (ref "R2") (pin "2") (pinfunction "2_2") (pintype "passive"))
      (node (ref "S1") (pin "3") (pinfunction "2_3") (pintype "passive"))
    )
    (net (code "59") (name "Net-(S2-2)") (class "Default")
      (node (ref "R3") (pin "1") (pinfunction "1_1") (pintype "passive"))
      (node (ref "R4") (pin "2") (pinfunction "2_2") (pintype "passive"))
      (node (ref "S2") (pin "3") (pinfunction "2_3") (pintype "passive"))
    )
    (net (code "60") (name "Net-(S3-2)") (class "Default")
      (node (ref "R5") (pin "1") (pinfunction "1_1") (pintype "passive"))
      (node (ref "R6") (pin "2") (pinfunction "2_2") (pintype "passive"))
      (node (ref "S3") (pin "3") (pinfunction "2_3") (pintype "passive"))
    )
    (net (code "61") (name "Net-(S4-2)") (class "Default")
      (node (ref "R7") (pin "1") (pinfunction "1_1") (pintype "passive"))
      (node (ref "R8") (pin "2") (pinfunction "2_2") (pintype "passive"))
      (node (ref "S4") (pin "3") (pinfunction "2_3") (pintype "passive"))
    )
    (net (code "62") (name "Net-(S5-2)") (class "Default")
      (node (ref "R10") (pin "2") (pinfunction "2_2") (pintype "passive"))
      (node (ref "R9") (pin "1") (pinfunction "1_1") (pintype "passive"))
      (node (ref "S5") (pin "3") (pinfunction "2_3") (pintype "passive"))
    )
    (net (code "63") (name "Net-(U2-ANODE)") (class "Default")
      (node (ref "C10") (pin "2") (pinfunction "2_2") (pintype "passive"))
      (node (ref "R31") (pin "1") (pinfunction "1_1") (pintype "passive"))
      (node (ref "R32") (pin "1") (pinfunction "1_1") (pintype "passive"))
      (node (ref "U2") (pin "2") (pinfunction "ANODE_2") (pintype "passive"))
    )
    (net (code "64") (name "Net-(U5-VIN+)") (class "Default")
      (node (ref "R32") (pin "2") (pinfunction "2_2") (pintype "passive"))
      (node (ref "R33") (pin "1") (pinfunction "1_1") (pintype "passive"))
      (node (ref "U5") (pin "3") (pinfunction "VIN+_3") (pintype "bidirectional"))
    )
    (net (code "65") (name "Net-(U5-VIN-)") (class "Default")
      (node (ref "R34") (pin "2") (pinfunction "2_2") (pintype "passive"))
      (node (ref "R35") (pin "1") (pinfunction "1_1") (pintype "passive"))
      (node (ref "U5") (pin "4") (pinfunction "VIN-_4") (pintype "bidirectional"))
    )
    (net (code "66") (name "Net-(U6-BST)") (class "Default")
      (node (ref "C14") (pin "2") (pinfunction "2_2") (pintype "passive"))
      (node (ref "U6") (pin "6") (pinfunction "BST_6") (pintype "bidirectional"))
    )
    (net (code "67") (name "Net-(U6-FB)") (class "Default")
      (node (ref "R38") (pin "1") (pinfunction "1_1") (pintype "passive"))
      (node (ref "R39") (pin "2") (pinfunction "2_2") (pintype "passive"))
      (node (ref "U6") (pin "4") (pinfunction "FB_4") (pintype "bidirectional"))
    )
    (net (code "68") (name "Net-(U6-SW)") (class "Default")
      (node (ref "C14") (pin "1") (pinfunction "1_1") (pintype "passive"))
      (node (ref "L1") (pin "1") (pinfunction "1_1") (pintype "bidirectional"))
      (node (ref "U6") (pin "2") (pinfunction "SW_2") (pintype "bidirectional"))
    )
    (net (code "69") (name "VCC") (class "Default")
      (node (ref "C12") (pin "2") (pinfunction "2_2") (pintype "passive"))
      (node (ref "C15") (pin "2") (pinfunction "2_2") (pintype "passive"))
      (node (ref "C16") (pin "2") (pinfunction "2_2") (pintype "passive"))
      (node (ref "C18") (pin "2") (pinfunction "2_2") (pintype "passive"))
      (node (ref "D1") (pin "2") (pinfunction "C2_2") (pintype "passive"))
      (node (ref "D2") (pin "2") (pinfunction "C2_2") (pintype "passive"))
      (node (ref "DISPLAY") (pin "2") (pinfunction "VCC_2") (pintype "bidirectional"))
      (node (ref "HALL_SIM") (pin "1") (pinfunction "1_1") (pintype "passive"))
      (node (ref "HALL_SIM") (pin "2") (pinfunction "2_2") (pintype "passive"))
      (node (ref "IR_SENSOR") (pin "3") (pinfunction "3_3") (pintype "bidirectional"))
      (node (ref "L1") (pin "2") (pinfunction "2_2") (pintype "bidirectional"))
      (node (ref "OUT_MOTOR_DRIVER") (pin "10") (pinfunction "10_10") (pintype "passive"))
      (node (ref "R1") (pin "2") (pinfunction "2_2") (pintype "passive"))
      (node (ref "R11") (pin "2") (pinfunction "2_2") (pintype "passive"))
      (node (ref "R14") (pin "2") (pinfunction "2_2") (pintype "passive"))
      (node (ref "R17") (pin "2") (pinfunction "2_2") (pintype "passive"))
      (node (ref "R23") (pin "1") (pinfunction "1_1") (pintype "passive"))
      (node (ref "R26") (pin "1") (pinfunction "1_1") (pintype "passive"))
      (node (ref "R3") (pin "2") (pinfunction "2_2") (pintype "passive"))
      (node (ref "R31") (pin "2") (pinfunction "2_2") (pintype "passive"))
      (node (ref "R38") (pin "2") (pinfunction "2_2") (pintype "passive"))
      (node (ref "R5") (pin "2") (pinfunction "2_2") (pintype "passive"))
      (node (ref "R66") (pin "1") (pinfunction "1_1") (pintype "passive"))
      (node (ref "R7") (pin "2") (pinfunction "2_2") (pintype "passive"))
      (node (ref "R9") (pin "2") (pinfunction "2_2") (pintype "passive"))
      (node (ref "U1") (pin "8") (pinfunction "VDD_8") (pintype "passive"))
      (node (ref "U4") (pin "VBUS") (pinfunction "VBUS_VBUS") (pintype "bidirectional"))
      (node (ref "U5") (pin "5") (pinfunction "VDD_5") (pintype "bidirectional"))
      (node (ref "U7") (pin "24") (pinfunction "VCC_24") (pintype "bidirectional"))
      (node (ref "Z1") (pin "1") (pinfunction "K_1") (pintype "bidirectional"))
    )
    (net (code "70") (name "unconnected-(MOTOR_OUTPUT-Pad3)") (class "Default")
      (node (ref "MOTOR_OUTPUT") (pin "3") (pinfunction "3_3") (pintype "passive"))
    )
    (net (code "71") (name "unconnected-(MOTOR_OUTPUT-Pad4)") (class "Default")
      (node (ref "MOTOR_OUTPUT") (pin "4") (pinfunction "4_4") (pintype "passive"))
    )
    (net (code "72") (name "unconnected-(MOTOR_OUTPUT-Pad7)") (class "Default")
      (node (ref "MOTOR_OUTPUT") (pin "7") (pinfunction "7_7") (pintype "passive"))
    )
    (net (code "73") (name "unconnected-(MOTOR_OUTPUT-Pad8)") (class "Default")
      (node (ref "MOTOR_OUTPUT") (pin "8") (pinfunction "8_8") (pintype "passive"))
    )
    (net (code "74") (name "unconnected-(U2-NC-Pad3)") (class "Default")
      (node (ref "U2") (pin "3") (pinfunction "NC_3") (pintype "passive"))
    )
    (net (code "75") (name "unconnected-(U3-Pad3)") (class "Default")
      (node (ref "U3") (pin "3") (pinfunction "3_3") (pintype "passive"))
    )
    (net (code "76") (name "unconnected-(U3-Pad4)") (class "Default")
      (node (ref "U3") (pin "4") (pinfunction "4_4") (pintype "passive"))
    )
    (net (code "77") (name "unconnected-(U3-Pad5)") (class "Default")
      (node (ref "U3") (pin "5") (pinfunction "5_5") (pintype "passive"))
    )
    (net (code "78") (name "unconnected-(U4-GND-PadGND@5)") (class "Default")
      (node (ref "U4") (pin "GND@5") (pinfunction "GND_GND@5") (pintype "bidirectional"))
    )
    (net (code "79") (name "unconnected-(U4-Pad3V3)") (class "Default")
      (node (ref "U4") (pin "3V3") (pinfunction "3V3_3V3") (pintype "bidirectional"))
    )
    (net (code "80") (name "unconnected-(U4-Pad3V3_EN)") (class "Default")
      (node (ref "U4") (pin "3V3_EN") (pinfunction "3V3_EN_3V3_EN") (pintype "bidirectional"))
    )
    (net (code "81") (name "unconnected-(U4-PadADC_VREF)") (class "Default")
      (node (ref "U4") (pin "ADC_VREF") (pinfunction "ADC_VREF_ADC_VREF") (pintype "bidirectional"))
    )
    (net (code "82") (name "unconnected-(U4-PadAGND)") (class "Default")
      (node (ref "U4") (pin "AGND") (pinfunction "AGND_AGND") (pintype "bidirectional"))
    )
    (net (code "83") (name "unconnected-(U4-PadRUN)") (class "Default")
      (node (ref "U4") (pin "RUN") (pinfunction "RUN_RUN") (pintype "bidirectional"))
    )
    (net (code "84") (name "unconnected-(U4-PadSWCLK)") (class "Default")
      (node (ref "U4") (pin "SWCLK") (pinfunction "SWCLK_SWCLK") (pintype "bidirectional"))
    )
    (net (code "85") (name "unconnected-(U4-PadSWDIO)") (class "Default")
      (node (ref "U4") (pin "SWDIO") (pinfunction "SWDIO_SWDIO") (pintype "bidirectional"))
    )
    (net (code "86") (name "unconnected-(U4-PadVSYS)") (class "Default")
      (node (ref "U4") (pin "VSYS") (pinfunction "VSYS_VSYS") (pintype "bidirectional"))
    )
    (net (code "87") (name "unconnected-(U7-INT-Pad1)") (class "Default")
      (node (ref "U7") (pin "1") (pinfunction "INT_1") (pintype "bidirectional"))
    )
    (net (code "88") (name "unconnected-(U7-P06-Pad10)") (class "Default")
      (node (ref "U7") (pin "10") (pinfunction "P06_10") (pintype "bidirectional"))
    )
    (net (code "89") (name "unconnected-(U7-P07-Pad11)") (class "Default")
      (node (ref "U7") (pin "11") (pinfunction "P07_11") (pintype "bidirectional"))
    )
    (net (code "90") (name "unconnected-(U7-P10-Pad13)") (class "Default")
      (node (ref "U7") (pin "13") (pinfunction "P10_13") (pintype "bidirectional"))
    )
    (net (code "91") (name "unconnected-(U7-P11-Pad14)") (class "Default")
      (node (ref "U7") (pin "14") (pinfunction "P11_14") (pintype "bidirectional"))
    )
    (net (code "92") (name "unconnected-(U7-P12-Pad15)") (class "Default")
      (node (ref "U7") (pin "15") (pinfunction "P12_15") (pintype "bidirectional"))
    )
    (net (code "93") (name "unconnected-(U7-P13-Pad16)") (class "Default")
      (node (ref "U7") (pin "16") (pinfunction "P13_16") (pintype "bidirectional"))
    )
    (net (code "94") (name "unconnected-(U7-P14-Pad17)") (class "Default")
      (node (ref "U7") (pin "17") (pinfunction "P14_17") (pintype "bidirectional"))
    )
    (net (code "95") (name "unconnected-(U7-P15-Pad18)") (class "Default")
      (node (ref "U7") (pin "18") (pinfunction "P15_18") (pintype "bidirectional"))
    )
    (net (code "96") (name "unconnected-(U7-P16-Pad19)") (class "Default")
      (node (ref "U7") (pin "19") (pinfunction "P16_19") (pintype "bidirectional"))
    )
    (net (code "97") (name "unconnected-(U7-P17-Pad20)") (class "Default")
      (node (ref "U7") (pin "20") (pinfunction "P17_20") (pintype "bidirectional"))
    )
  )
)
